# GM-UART-V2.net
KiCad netlist of a schematic drawn in EAGLE
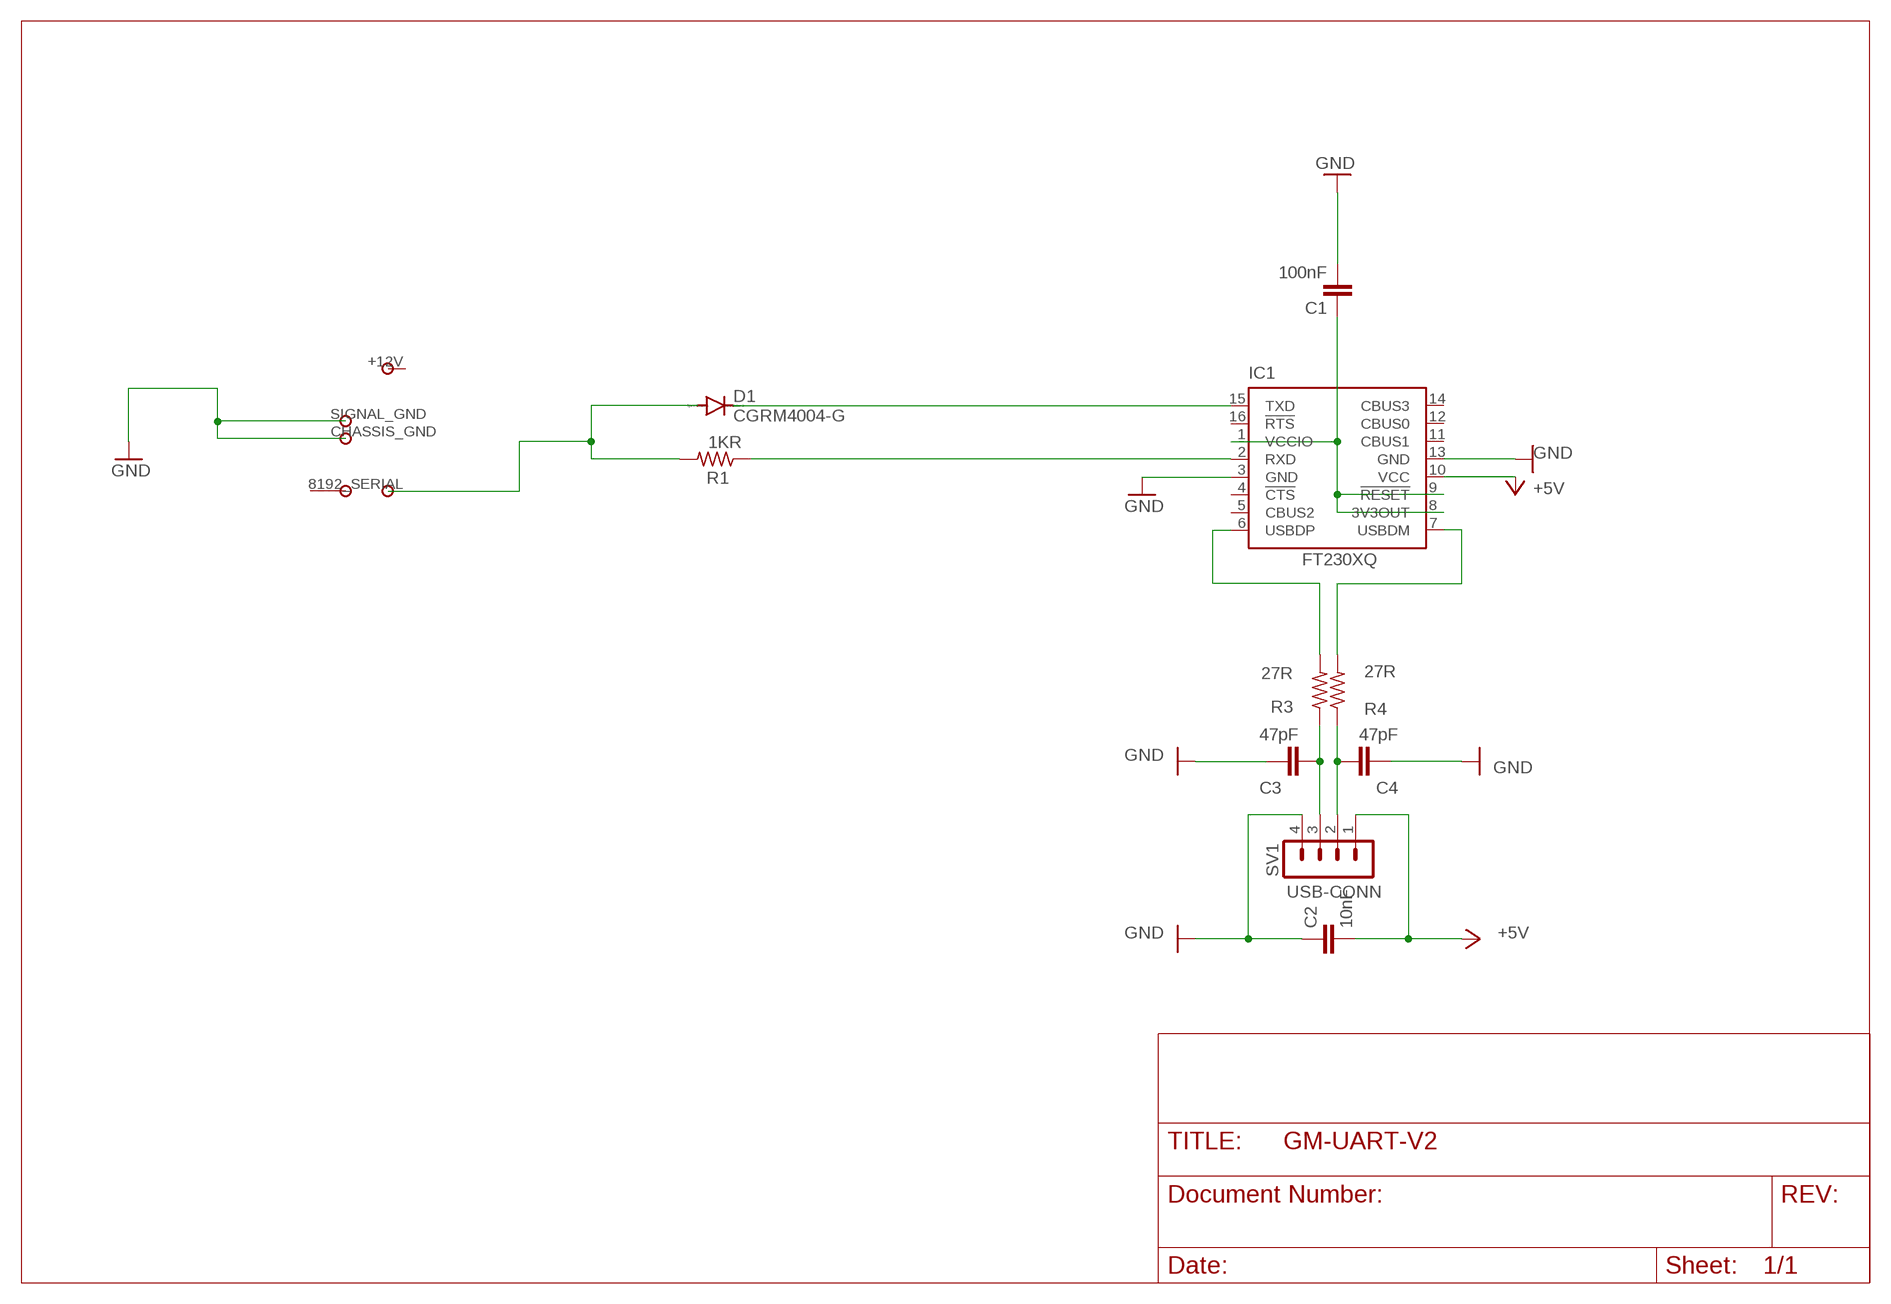
[diagram p0: schematic, sheet 1]

(export (version "E")
  (design (tool "Eeschema 10.0.6"))
  (components
    (comp (ref "C1")
      (value "100nF")
      (footprint "eagle-import:C0603K")
      (libsource (lib "eagle-import") (part "C-EUC0603K"))
    )
    (comp (ref "C2")
      (value "10nF")
      (footprint "eagle-import:C0603K")
      (libsource (lib "eagle-import") (part "C-EUC0603K"))
    )
    (comp (ref "C3")
      (value "47pF")
      (footprint "eagle-import:C0603K")
      (libsource (lib "eagle-import") (part "C-EUC0603K"))
    )
    (comp (ref "C4")
      (value "47pF")
      (footprint "eagle-import:C0603K")
      (libsource (lib "eagle-import") (part "C-EUC0603K"))
    )
    (comp (ref "D1")
      (value "CGRM4004-G")
      (footprint "eagle-import:SOD-123_MINI-SMA")
      (libsource (lib "eagle-import") (part "CGRM400-G4"))
    )
    (comp (ref "IC1")
      (value "FT230XQ")
      (footprint "eagle-import:QFN16")
      (libsource (lib "eagle-import") (part "FT230XQ"))
    )
    (comp (ref "R1")
      (value "1KR")
      (footprint "eagle-import:M0805")
      (libsource (lib "eagle-import") (part "R-US_M0805"))
    )
    (comp (ref "R3")
      (value "27R")
      (footprint "eagle-import:R0603")
      (libsource (lib "eagle-import") (part "R-US_R0603"))
    )
    (comp (ref "R4")
      (value "27R")
      (footprint "eagle-import:R0603")
      (libsource (lib "eagle-import") (part "R-US_R0603"))
    )
    (comp (ref "SV1")
      (value "USB-CONN")
      (footprint "eagle-import:MA04-1")
      (libsource (lib "eagle-import") (part "MA04-1"))
    )
    (comp (ref "U$2")
      (value "OBD2PLUG")
      (footprint "eagle-import:OBD2PLUG")
      (libsource (lib "eagle-import") (part "OBD2PLUG"))
    )
  )
  (nets
    (net (code "1") (name "+5V") (class "Default")
      (node (ref "C2") (pin "2") (pinfunction "2_2") (pintype "passive"))
      (node (ref "IC1") (pin "10") (pinfunction "VCC_10") (pintype "power_in"))
      (node (ref "SV1") (pin "1") (pinfunction "1_1") (pintype "passive"))
    )
    (net (code "2") (name "/+12V") (class "Default")
      (node (ref "U$2") (pin "+12V") (pinfunction "+12V_+12V") (pintype "power_in"))
    )
    (net (code "3") (name "GND") (class "Default")
      (node (ref "C1") (pin "2") (pinfunction "2_2") (pintype "passive"))
      (node (ref "C2") (pin "1") (pinfunction "1_1") (pintype "passive"))
      (node (ref "C3") (pin "2") (pinfunction "2_2") (pintype "passive"))
      (node (ref "C4") (pin "2") (pinfunction "2_2") (pintype "passive"))
      (node (ref "IC1") (pin "13") (pinfunction "GND_13") (pintype "power_in"))
      (node (ref "IC1") (pin "3") (pinfunction "GND_3") (pintype "power_in"))
      (node (ref "SV1") (pin "4") (pinfunction "4_4") (pintype "passive"))
      (node (ref "U$2") (pin "CHASSIS_GND") (pinfunction "CHASSIS_GND_CHASSIS_GND") (pintype "power_in"))
      (node (ref "U$2") (pin "SIGNAL_GND") (pinfunction "SIGNAL_GND_SIGNAL_GND") (pintype "power_in"))
    )
    (net (code "4") (name "Net-(C3-Pad1)") (class "Default")
      (node (ref "C3") (pin "1") (pinfunction "1_1") (pintype "passive"))
      (node (ref "R3") (pin "1") (pinfunction "1_1") (pintype "passive"))
      (node (ref "SV1") (pin "3") (pinfunction "3_3") (pintype "passive"))
    )
    (net (code "5") (name "Net-(C4-Pad1)") (class "Default")
      (node (ref "C4") (pin "1") (pinfunction "1_1") (pintype "passive"))
      (node (ref "R4") (pin "1") (pinfunction "1_1") (pintype "passive"))
      (node (ref "SV1") (pin "2") (pinfunction "2_2") (pintype "passive"))
    )
    (net (code "6") (name "Net-(D1-PadA)") (class "Default")
      (node (ref "D1") (pin "A") (pinfunction "A_A") (pintype "passive"))
      (node (ref "R1") (pin "2") (pinfunction "2_2") (pintype "passive"))
      (node (ref "U$2") (pin "8192_SERIAL") (pinfunction "8192_SERIAL_8192_SERIAL") (pintype "bidirectional"))
    )
    (net (code "7") (name "Net-(IC1-3V3OUT)") (class "Default")
      (node (ref "C1") (pin "1") (pinfunction "1_1") (pintype "passive"))
      (node (ref "IC1") (pin "1") (pinfunction "VCCIO_1") (pintype "power_in"))
      (node (ref "IC1") (pin "8") (pinfunction "3V3OUT_8") (pintype "output"))
      (node (ref "IC1") (pin "9") (pinfunction "~{RESET}_9") (pintype "input"))
    )
    (net (code "8") (name "Net-(IC1-RXD)") (class "Default")
      (node (ref "IC1") (pin "2") (pinfunction "RXD_2") (pintype "input"))
      (node (ref "R1") (pin "1") (pinfunction "1_1") (pintype "passive"))
    )
    (net (code "9") (name "Net-(IC1-TXD)") (class "Default")
      (node (ref "D1") (pin "C") (pinfunction "C_C") (pintype "passive"))
      (node (ref "IC1") (pin "15") (pinfunction "TXD_15") (pintype "output"))
    )
    (net (code "10") (name "Net-(IC1-USBDM)") (class "Default")
      (node (ref "IC1") (pin "7") (pinfunction "USBDM_7") (pintype "input"))
      (node (ref "R4") (pin "2") (pinfunction "2_2") (pintype "passive"))
    )
    (net (code "11") (name "Net-(IC1-USBDP)") (class "Default")
      (node (ref "IC1") (pin "6") (pinfunction "USBDP_6") (pintype "input"))
      (node (ref "R3") (pin "2") (pinfunction "2_2") (pintype "passive"))
    )
    (net (code "12") (name "unconnected-(IC1-CBUS0-Pad12)") (class "Default")
      (node (ref "IC1") (pin "12") (pinfunction "CBUS0_12") (pintype "bidirectional"))
    )
    (net (code "13") (name "unconnected-(IC1-CBUS1-Pad11)") (class "Default")
      (node (ref "IC1") (pin "11") (pinfunction "CBUS1_11") (pintype "bidirectional"))
    )
    (net (code "14") (name "unconnected-(IC1-CBUS2-Pad5)") (class "Default")
      (node (ref "IC1") (pin "5") (pinfunction "CBUS2_5") (pintype "bidirectional"))
    )
    (net (code "15") (name "unconnected-(IC1-CBUS3-Pad14)") (class "Default")
      (node (ref "IC1") (pin "14") (pinfunction "CBUS3_14") (pintype "bidirectional"))
    )
    (net (code "16") (name "unconnected-(IC1-~{CTS}-Pad4)") (class "Default")
      (node (ref "IC1") (pin "4") (pinfunction "~{CTS}_4") (pintype "input"))
    )
    (net (code "17") (name "unconnected-(IC1-~{RTS}-Pad16)") (class "Default")
      (node (ref "IC1") (pin "16") (pinfunction "~{RTS}_16") (pintype "output"))
    )
    (net (code "18") (name "unconnected-(U$2-PadP$1)") (class "Default")
      (node (ref "U$2") (pin "P$1") (pinfunction "P$1_P$1") (pintype "no_connect"))
    )
  )
)
